# LightSensorWiring.net
KiCad netlist of a schematic drawn in EAGLE
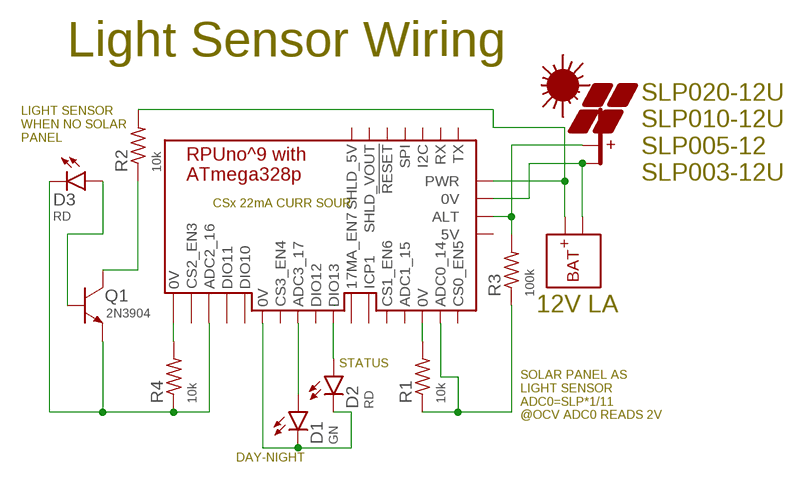
[diagram p0: schematic, sheet 1]

(export (version "E")
  (design (tool "Eeschema 10.0.6"))
  (components
    (comp (ref "BM1")
      (value "RPUNO")
      (footprint "eagle-import:NA-30")
      (libsource (lib "eagle-import") (part "RPUNO"))
    )
    (comp (ref "D1")
      (value "GN")
      (footprint "eagle-import:LED5MM")
      (libsource (lib "eagle-import") (part "LED5MM"))
    )
    (comp (ref "D2")
      (value "RD")
      (footprint "eagle-import:LED5MM")
      (libsource (lib "eagle-import") (part "LED5MM"))
    )
    (comp (ref "D3")
      (value "RD")
      (footprint "eagle-import:LED5MM")
      (libsource (lib "eagle-import") (part "LED5MM"))
    )
    (comp (ref "PV4")
      (value "PV")
      (footprint "eagle-import:NA-30")
      (libsource (lib "eagle-import") (part "PV"))
    )
    (comp (ref "Q1")
      (value "2N3904")
      (footprint "eagle-import:SOT23")
      (libsource (lib "eagle-import") (part "NPNSOT23"))
    )
    (comp (ref "R1")
      (value "10k")
      (footprint "eagle-import:C0805(2012)")
      (libsource (lib "eagle-import") (part "R0805"))
    )
    (comp (ref "R2")
      (value "10k")
      (footprint "eagle-import:C0805(2012)")
      (libsource (lib "eagle-import") (part "R0805"))
    )
    (comp (ref "R3")
      (value "100k")
      (footprint "eagle-import:C0805(2012)")
      (libsource (lib "eagle-import") (part "R0805"))
    )
    (comp (ref "R4")
      (value "10k")
      (footprint "eagle-import:C0805(2012)")
      (libsource (lib "eagle-import") (part "R0805"))
    )
    (comp (ref "U$7")
      (value "BAT")
      (footprint "eagle-import:NA-30")
      (libsource (lib "eagle-import") (part "BAT"))
    )
  )
  (nets
    (net (code "1") (name "Net-(BM1-0V-Pad26)") (class "Default")
      (node (ref "BM1") (pin "26") (pinfunction "0V_26") (pintype "bidirectional"))
      (node (ref "R1") (pin "2") (pinfunction "2_2") (pintype "passive"))
    )
    (net (code "2") (name "Net-(BM1-0V-Pad27)") (class "Default")
      (node (ref "BM1") (pin "27") (pinfunction "0V_27") (pintype "bidirectional"))
      (node (ref "R4") (pin "2") (pinfunction "2_2") (pintype "passive"))
    )
    (net (code "3") (name "Net-(BM1-0V-Pad28)") (class "Default")
      (node (ref "BM1") (pin "28") (pinfunction "0V_28") (pintype "bidirectional"))
      (node (ref "D1") (pin "K") (pinfunction "K_K") (pintype "passive"))
      (node (ref "D2") (pin "K") (pinfunction "K_K") (pintype "passive"))
    )
    (net (code "4") (name "Net-(BM1-ADC0_14)") (class "Default")
      (node (ref "BM1") (pin "11") (pinfunction "ADC0_14_11") (pintype "bidirectional"))
      (node (ref "R1") (pin "1") (pinfunction "1_1") (pintype "passive"))
      (node (ref "R3") (pin "1") (pinfunction "1_1") (pintype "passive"))
    )
    (net (code "5") (name "Net-(BM1-ADC2_16)") (class "Default")
      (node (ref "BM1") (pin "13") (pinfunction "ADC2_16_13") (pintype "bidirectional"))
      (node (ref "D3") (pin "K") (pinfunction "K_K") (pintype "passive"))
      (node (ref "Q1") (pin "E") (pinfunction "E_E") (pintype "passive"))
      (node (ref "R4") (pin "1") (pinfunction "1_1") (pintype "passive"))
    )
    (net (code "6") (name "Net-(BM1-ADC3_17)") (class "Default")
      (node (ref "BM1") (pin "16") (pinfunction "ADC3_17_16") (pintype "bidirectional"))
      (node (ref "D1") (pin "A") (pinfunction "A_A") (pintype "passive"))
    )
    (net (code "7") (name "Net-(BM1-ALT)") (class "Default")
      (node (ref "BM1") (pin "20") (pinfunction "ALT_20") (pintype "bidirectional"))
      (node (ref "PV4") (pin "1") (pinfunction "+PV_1") (pintype "bidirectional"))
      (node (ref "R3") (pin "2") (pinfunction "2_2") (pintype "passive"))
    )
    (net (code "8") (name "Net-(BM1-DIO13)") (class "Default")
      (node (ref "BM1") (pin "18") (pinfunction "DIO13_18") (pintype "bidirectional"))
      (node (ref "D2") (pin "A") (pinfunction "A_A") (pintype "passive"))
    )
    (net (code "9") (name "Net-(BM1-PWR)") (class "Default")
      (node (ref "BM1") (pin "8") (pinfunction "PWR_8") (pintype "bidirectional"))
      (node (ref "R2") (pin "2") (pinfunction "2_2") (pintype "passive"))
      (node (ref "U$7") (pin "1") (pinfunction "+BAT_1") (pintype "bidirectional"))
    )
    (net (code "10") (name "Net-(D3-PadA)") (class "Default")
      (node (ref "D3") (pin "A") (pinfunction "A_A") (pintype "passive"))
      (node (ref "Q1") (pin "B") (pinfunction "B_B") (pintype "passive"))
    )
    (net (code "11") (name "Net-(PV4--PV)") (class "Default")
      (node (ref "BM1") (pin "9") (pinfunction "0V_9") (pintype "bidirectional"))
      (node (ref "PV4") (pin "2") (pinfunction "-PV_2") (pintype "bidirectional"))
      (node (ref "U$7") (pin "2") (pinfunction "-BAT_2") (pintype "bidirectional"))
    )
    (net (code "12") (name "Net-(Q1-PadC)") (class "Default")
      (node (ref "Q1") (pin "C") (pinfunction "C_C") (pintype "passive"))
      (node (ref "R2") (pin "1") (pinfunction "1_1") (pintype "passive"))
    )
    (net (code "13") (name "unconnected-(BM1-5V-Pad19)") (class "Default")
      (node (ref "BM1") (pin "19") (pinfunction "5V_19") (pintype "bidirectional"))
    )
    (net (code "14") (name "unconnected-(BM1-17MA_EN7-Pad21)") (class "Default")
      (node (ref "BM1") (pin "21") (pinfunction "17MA_EN7_21") (pintype "bidirectional"))
    )
    (net (code "15") (name "unconnected-(BM1-ADC1_15-Pad10)") (class "Default")
      (node (ref "BM1") (pin "10") (pinfunction "ADC1_15_10") (pintype "bidirectional"))
    )
    (net (code "16") (name "unconnected-(BM1-CS0_EN5-Pad23)") (class "Default")
      (node (ref "BM1") (pin "23") (pinfunction "CS0_EN5_23") (pintype "bidirectional"))
    )
    (net (code "17") (name "unconnected-(BM1-CS1_EN6-Pad22)") (class "Default")
      (node (ref "BM1") (pin "22") (pinfunction "CS1_EN6_22") (pintype "bidirectional"))
    )
    (net (code "18") (name "unconnected-(BM1-CS2_EN3-Pad24)") (class "Default")
      (node (ref "BM1") (pin "24") (pinfunction "CS2_EN3_24") (pintype "bidirectional"))
    )
    (net (code "19") (name "unconnected-(BM1-CS3_EN4-Pad29)") (class "Default")
      (node (ref "BM1") (pin "29") (pinfunction "CS3_EN4_29") (pintype "bidirectional"))
    )
    (net (code "20") (name "unconnected-(BM1-DIO10-Pad15)") (class "Default")
      (node (ref "BM1") (pin "15") (pinfunction "DIO10_15") (pintype "bidirectional"))
    )
    (net (code "21") (name "unconnected-(BM1-DIO11-Pad14)") (class "Default")
      (node (ref "BM1") (pin "14") (pinfunction "DIO11_14") (pintype "bidirectional"))
    )
    (net (code "22") (name "unconnected-(BM1-DIO12-Pad17)") (class "Default")
      (node (ref "BM1") (pin "17") (pinfunction "DIO12_17") (pintype "bidirectional"))
    )
    (net (code "23") (name "unconnected-(BM1-I2C-Pad3)") (class "Default")
      (node (ref "BM1") (pin "3") (pinfunction "I2C_3") (pintype "bidirectional"))
    )
    (net (code "24") (name "unconnected-(BM1-ICP1-Pad12)") (class "Default")
      (node (ref "BM1") (pin "12") (pinfunction "ICP1_12") (pintype "bidirectional"))
    )
    (net (code "25") (name "unconnected-(BM1-RX-Pad2)") (class "Default")
      (node (ref "BM1") (pin "2") (pinfunction "RX_2") (pintype "bidirectional"))
    )
    (net (code "26") (name "unconnected-(BM1-SHLD_5V-Pad6)") (class "Default")
      (node (ref "BM1") (pin "6") (pinfunction "SHLD_5V_6") (pintype "bidirectional"))
    )
    (net (code "27") (name "unconnected-(BM1-SHLD_VOUT-Pad7)") (class "Default")
      (node (ref "BM1") (pin "7") (pinfunction "SHLD_VOUT_7") (pintype "bidirectional"))
    )
    (net (code "28") (name "unconnected-(BM1-SPI-Pad4)") (class "Default")
      (node (ref "BM1") (pin "4") (pinfunction "SPI_4") (pintype "bidirectional"))
    )
    (net (code "29") (name "unconnected-(BM1-TX-Pad1)") (class "Default")
      (node (ref "BM1") (pin "1") (pinfunction "TX_1") (pintype "bidirectional"))
    )
    (net (code "30") (name "unconnected-(BM1-~{RESET}-Pad5)") (class "Default")
      (node (ref "BM1") (pin "5") (pinfunction "~{RESET}_5") (pintype "bidirectional"))
    )
  )
)
